# uc.net
KiCad netlist of a schematic drawn in Altium Designer
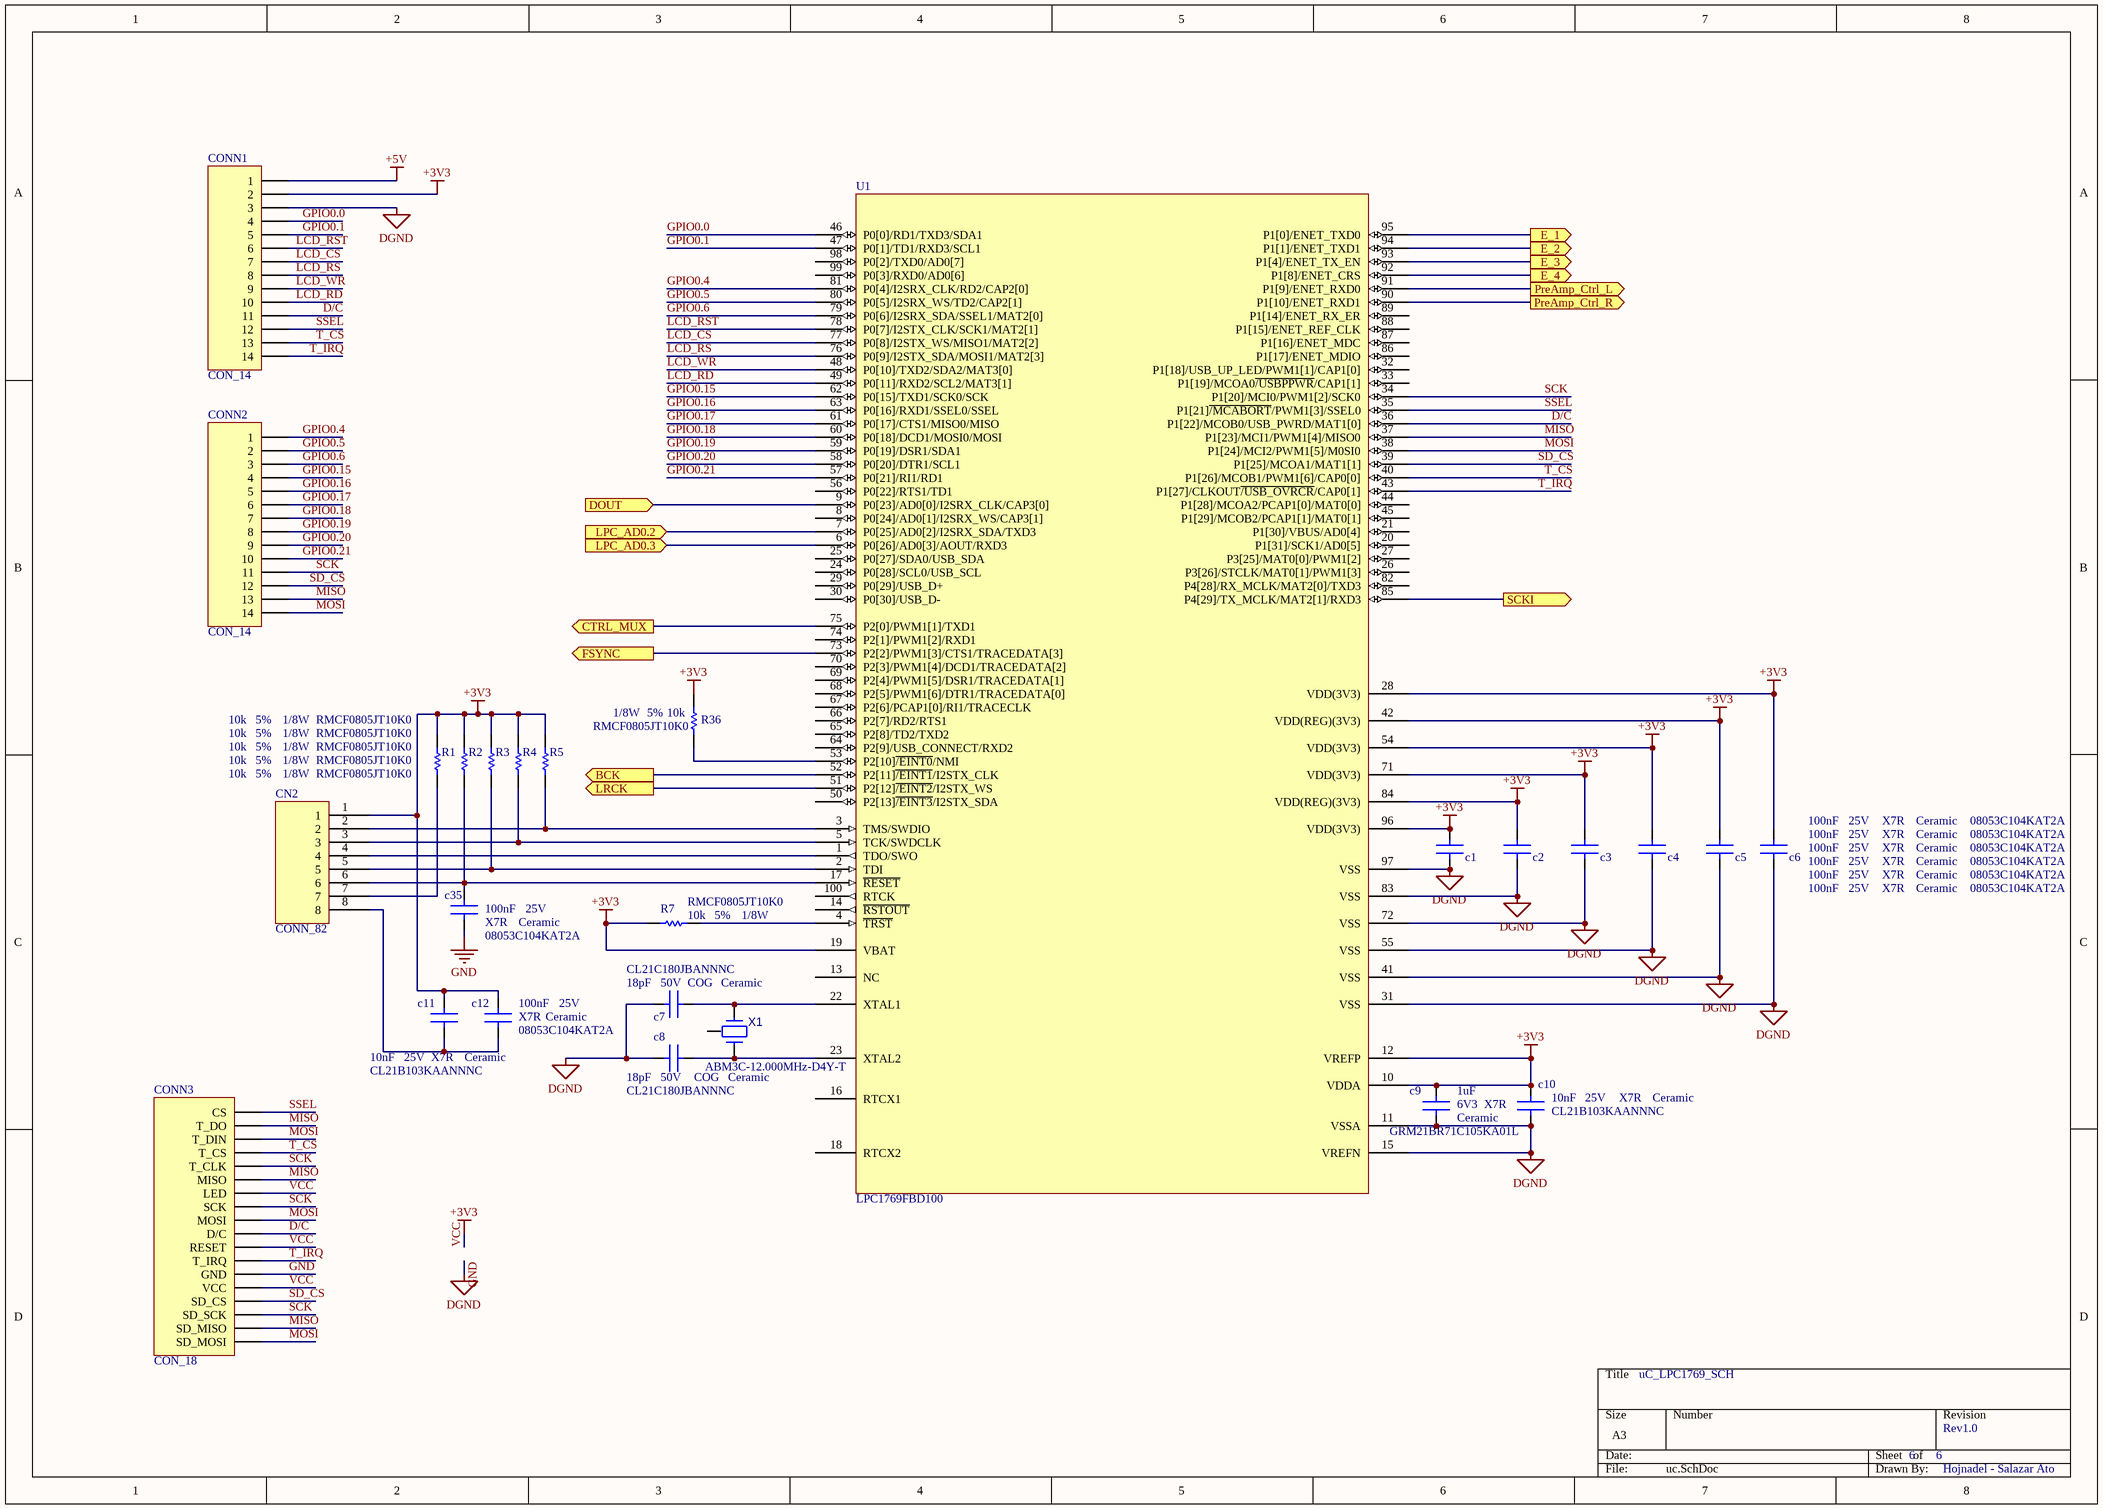
[diagram p0: uc.SchDoc]

(export (version "E")
  (design (tool "Eeschema 10.0.6"))
  (components
    (comp (ref "c1")
      (value "100nF 25V X7R Ceramic")
      (footprint "C_0805")
      (description "Capacitor")
      (fields
        (field (name "C") "100nF")
        (field (name "V") "25V")
        (field (name "PART NUMBER") "08053C104KAT2A")
        (field (name "TEMP COEF") "X7R")
        (field (name "MATERIAL") "Ceramic")
      )
      (libsource (lib "TDII_Lib_V2") (part "Cap1"))
    )
    (comp (ref "c2")
      (value "100nF 25V X7R Ceramic")
      (footprint "C_0805")
      (description "Capacitor")
      (fields
        (field (name "C") "100nF")
        (field (name "V") "25V")
        (field (name "PART NUMBER") "08053C104KAT2A")
        (field (name "TEMP COEF") "X7R")
        (field (name "MATERIAL") "Ceramic")
      )
      (libsource (lib "TDII_Lib_V2") (part "Cap1"))
    )
    (comp (ref "c3")
      (value "100nF 25V X7R Ceramic")
      (footprint "C_0805")
      (description "Capacitor")
      (fields
        (field (name "C") "100nF")
        (field (name "V") "25V")
        (field (name "PART NUMBER") "08053C104KAT2A")
        (field (name "TEMP COEF") "X7R")
        (field (name "MATERIAL") "Ceramic")
      )
      (libsource (lib "TDII_Lib_V2") (part "Cap1"))
    )
    (comp (ref "c4")
      (value "100nF 25V X7R Ceramic")
      (footprint "C_0805")
      (description "Capacitor")
      (fields
        (field (name "C") "100nF")
        (field (name "V") "25V")
        (field (name "PART NUMBER") "08053C104KAT2A")
        (field (name "TEMP COEF") "X7R")
        (field (name "MATERIAL") "Ceramic")
      )
      (libsource (lib "TDII_Lib_V2") (part "Cap1"))
    )
    (comp (ref "c5")
      (value "100nF 25V X7R Ceramic")
      (footprint "C_0805")
      (description "Capacitor")
      (fields
        (field (name "C") "100nF")
        (field (name "V") "25V")
        (field (name "PART NUMBER") "08053C104KAT2A")
        (field (name "TEMP COEF") "X7R")
        (field (name "MATERIAL") "Ceramic")
      )
      (libsource (lib "TDII_Lib_V2") (part "Cap1"))
    )
    (comp (ref "c6")
      (value "100nF 25V X7R Ceramic")
      (footprint "C_0805")
      (description "Capacitor")
      (fields
        (field (name "C") "100nF")
        (field (name "V") "25V")
        (field (name "PART NUMBER") "08053C104KAT2A")
        (field (name "TEMP COEF") "X7R")
        (field (name "MATERIAL") "Ceramic")
      )
      (libsource (lib "TDII_Lib_V2") (part "Cap1"))
    )
    (comp (ref "c7")
      (value "18pF 50V COG Ceramic")
      (footprint "C_0805")
      (description "Capacitor")
      (fields
        (field (name "C") "18pF")
        (field (name "V") "50V")
        (field (name "PART NUMBER") "CL21C180JBANNNC")
        (field (name "TEMP COEF") "COG")
        (field (name "MATERIAL") "Ceramic")
      )
      (libsource (lib "TDII_Lib_V2") (part "Cap1"))
    )
    (comp (ref "c8")
      (value "18pF 50V COG Ceramic")
      (footprint "C_0805")
      (description "Capacitor")
      (fields
        (field (name "C") "18pF")
        (field (name "V") "50V")
        (field (name "PART NUMBER") "CL21C180JBANNNC")
        (field (name "TEMP COEF") "COG")
        (field (name "MATERIAL") "Ceramic")
      )
      (libsource (lib "TDII_Lib_V2") (part "Cap1"))
    )
    (comp (ref "c9")
      (value "1uF 6V3 X7R Ceramic")
      (footprint "C_0805")
      (description "Capacitor")
      (fields
        (field (name "C") "1uF")
        (field (name "V") "6V3")
        (field (name "PART NUMBER") "GRM21BR71C105KA01L")
        (field (name "TEMP COEF") "X7R")
        (field (name "MATERIAL") "Ceramic")
      )
      (libsource (lib "TDII_Lib_V2") (part "Cap1"))
    )
    (comp (ref "c10")
      (value "10nF 25V X7R Ceramic")
      (footprint "C_0805")
      (description "Capacitor")
      (fields
        (field (name "C") "10nF")
        (field (name "V") "25V")
        (field (name "PART NUMBER") "CL21B103KAANNNC")
        (field (name "TEMP COEF") "X7R")
        (field (name "MATERIAL") "Ceramic")
      )
      (libsource (lib "TDII_Lib_V2") (part "Cap1"))
    )
    (comp (ref "c11")
      (value "10nF 25V X7R Ceramic")
      (footprint "C_0805")
      (description "Capacitor")
      (fields
        (field (name "C") "10nF")
        (field (name "V") "25V")
        (field (name "PART NUMBER") "CL21B103KAANNNC")
        (field (name "TEMP COEF") "X7R")
        (field (name "MATERIAL") "Ceramic")
      )
      (libsource (lib "TDII_Lib_V2") (part "Cap1"))
    )
    (comp (ref "c12")
      (value "100nF 25V X7R Ceramic")
      (footprint "C_0805")
      (description "Capacitor")
      (fields
        (field (name "C") "100nF")
        (field (name "V") "25V")
        (field (name "PART NUMBER") "08053C104KAT2A")
        (field (name "TEMP COEF") "X7R")
        (field (name "MATERIAL") "Ceramic")
      )
      (libsource (lib "TDII_Lib_V2") (part "C?"))
    )
    (comp (ref "c35")
      (value "100nF 25V X7R Ceramic")
      (footprint "C_0805")
      (description "Capacitor")
      (fields
        (field (name "C") "100nF")
        (field (name "V") "25V")
        (field (name "TEMP COEF") "X7R")
        (field (name "PART NUMBER") "08053C104KAT2A")
        (field (name "MATERIAL") "Ceramic")
      )
      (libsource (lib "TDII_Lib_V2") (part "C?"))
    )
    (comp (ref "CN2")
      (value "CONN_82")
      (footprint "HDR_M_08P_0.1")
      (libsource (lib "TDII_Lib") (part "CONN_82"))
    )
    (comp (ref "CONN1")
      (value "CON_14")
      (footprint "1x14x2.54 Pin Header TH V")
      (description "CONN TFT 3.5")
      (libsource (lib "TDII_Lib_V2") (part "CON_14"))
    )
    (comp (ref "CONN2")
      (value "CON_14")
      (footprint "1x14x2.54 Pin Header TH V")
      (description "CONN TFT 3.5")
      (libsource (lib "TDII_Lib_V2") (part "CON_14"))
    )
    (comp (ref "CONN3")
      (value "CON_18")
      (footprint "2x9x2.54 Pin Header TH V")
      (description "CON_TFT_2.8")
      (libsource (lib "TDII_Lib_V2") (part "CON_18"))
    )
    (comp (ref "R1")
      (value "10k")
      (footprint "R_0805")
      (description "Resistor")
      (fields
        (field (name "POWER") "1/8W")
        (field (name "PART NUMBER") "RMCF0805JT10K0")
        (field (name "TOLERANCE") "5%")
        (field (name "Comment") "10k 5% 1/8W")
      )
      (libsource (lib "TDII_Lib") (part "Res1"))
    )
    (comp (ref "R2")
      (value "10k")
      (footprint "R_0805")
      (description "Resistor")
      (fields
        (field (name "PART NUMBER") "RMCF0805JT10K0")
        (field (name "TOLERANCE") "5%")
        (field (name "POWER") "1/8W")
        (field (name "Comment") "10k 5% 1/8W")
      )
      (libsource (lib "TDII_Lib") (part "Res1"))
    )
    (comp (ref "R3")
      (value "10k")
      (footprint "R_0805")
      (description "Resistor")
      (fields
        (field (name "POWER") "1/8W")
        (field (name "PART NUMBER") "RMCF0805JT10K0")
        (field (name "TOLERANCE") "5%")
        (field (name "Comment") "10k 5% 1/8W")
      )
      (libsource (lib "TDII_Lib") (part "Res1"))
    )
    (comp (ref "R4")
      (value "10k")
      (footprint "R_0805")
      (description "Resistor")
      (fields
        (field (name "POWER") "1/8W")
        (field (name "PART NUMBER") "RMCF0805JT10K0")
        (field (name "TOLERANCE") "5%")
        (field (name "Comment") "10k 5% 1/8W")
      )
      (libsource (lib "TDII_Lib") (part "Res1"))
    )
    (comp (ref "R5")
      (value "10k")
      (footprint "R_0805")
      (description "Resistor")
      (fields
        (field (name "POWER") "1/8W")
        (field (name "PART NUMBER") "RMCF0805JT10K0")
        (field (name "TOLERANCE") "5%")
        (field (name "Comment") "10k 5% 1/8W")
      )
      (libsource (lib "TDII_Lib") (part "Res1"))
    )
    (comp (ref "R7")
      (value "10k")
      (footprint "R_0805")
      (description "Resistor")
      (fields
        (field (name "POWER") "1/8W")
        (field (name "PART NUMBER") "RMCF0805JT10K0")
        (field (name "TOLERANCE") "5%")
        (field (name "Comment") "10k 5% 1/8W")
      )
      (libsource (lib "TDII_Lib") (part "Res1"))
    )
    (comp (ref "R36")
      (value "10k")
      (footprint "R_0805")
      (description "Resistor")
      (fields
        (field (name "POWER") "1/8W")
        (field (name "PART NUMBER") "RMCF0805JT10K0")
        (field (name "TOLERANCE") "5%")
        (field (name "Comment") "10k 5% 1/8W")
      )
      (libsource (lib "TDII_Lib_V2") (part "Res1"))
    )
    (comp (ref "U1")
      (value "LPC1769FBD100")
      (footprint "LQFP100")
      (description "CPU Cortex M3")
      (libsource (lib "TDII_Lib_V2") (part "LPC1768FBD100"))
    )
    (comp (ref "X1")
      (value "XTAL_HF")
      (footprint "ABMC_XTAL")
      (description "Crystal")
      (fields (field (name "PART NUMBER") "ABM3C-12.000MHz-D4Y-T"))
      (libsource (lib "TDII_Lib_V2") (part "XTAL_HF"))
    )
  )
  (nets
    (net (code "1") (name "+3V3") (class "Default")
      (node (ref "CN2") (pin "1") (pinfunction "1_1") (pintype "passive"))
      (node (ref "CONN1") (pin "2") (pinfunction "2_2") (pintype "passive"))
      (node (ref "CONN3") (pin "11") (pinfunction "RESET_11") (pintype "passive"))
      (node (ref "CONN3") (pin "14") (pinfunction "VCC_14") (pintype "passive"))
      (node (ref "CONN3") (pin "7") (pinfunction "LED_7") (pintype "passive"))
      (node (ref "R1") (pin "2") (pinfunction "2_2") (pintype "passive"))
      (node (ref "R2") (pin "2") (pinfunction "2_2") (pintype "passive"))
      (node (ref "R3") (pin "2") (pinfunction "2_2") (pintype "passive"))
      (node (ref "R36") (pin "2") (pinfunction "2_2") (pintype "passive"))
      (node (ref "R4") (pin "2") (pinfunction "2_2") (pintype "passive"))
      (node (ref "R5") (pin "2") (pinfunction "2_2") (pintype "passive"))
      (node (ref "R7") (pin "2") (pinfunction "2_2") (pintype "passive"))
      (node (ref "U1") (pin "10") (pinfunction "VDDA_10") (pintype "power_in"))
      (node (ref "U1") (pin "12") (pinfunction "VREFP_12") (pintype "power_in"))
      (node (ref "U1") (pin "19") (pinfunction "VBAT_19") (pintype "power_in"))
      (node (ref "U1") (pin "28") (pinfunction "VDD(3V3)_28") (pintype "power_in"))
      (node (ref "U1") (pin "42") (pinfunction "VDD(REG)(3V3)_42") (pintype "power_in"))
      (node (ref "U1") (pin "54") (pinfunction "VDD(3V3)_54") (pintype "power_in"))
      (node (ref "U1") (pin "71") (pinfunction "VDD(3V3)_71") (pintype "power_in"))
      (node (ref "U1") (pin "84") (pinfunction "VDD(REG)(3V3)_84") (pintype "power_in"))
      (node (ref "U1") (pin "96") (pinfunction "VDD(3V3)_96") (pintype "power_in"))
      (node (ref "c1") (pin "1") (pinfunction "1_1") (pintype "passive"))
      (node (ref "c10") (pin "1") (pinfunction "1_1") (pintype "passive"))
      (node (ref "c11") (pin "1") (pinfunction "1_1") (pintype "passive"))
      (node (ref "c12") (pin "1") (pinfunction "1_1") (pintype "passive"))
      (node (ref "c2") (pin "1") (pinfunction "1_1") (pintype "passive"))
      (node (ref "c3") (pin "1") (pinfunction "1_1") (pintype "passive"))
      (node (ref "c4") (pin "1") (pinfunction "1_1") (pintype "passive"))
      (node (ref "c5") (pin "1") (pinfunction "1_1") (pintype "passive"))
      (node (ref "c6") (pin "1") (pinfunction "1_1") (pintype "passive"))
      (node (ref "c9") (pin "1") (pinfunction "1_1") (pintype "passive"))
    )
    (net (code "2") (name "+5V") (class "Default")
      (node (ref "CONN1") (pin "1") (pinfunction "1_1") (pintype "passive"))
    )
    (net (code "3") (name "/BCK") (class "Default")
      (node (ref "U1") (pin "52") (pinfunction "P2[11]~{/EINT1}/I2STX_CLK_52") (pintype "bidirectional"))
    )
    (net (code "4") (name "/CTRL_MUX") (class "Default")
      (node (ref "U1") (pin "75") (pinfunction "P2[0]/PWM1[1]/TXD1_75") (pintype "bidirectional"))
    )
    (net (code "5") (name "/DOUT") (class "Default")
      (node (ref "U1") (pin "9") (pinfunction "P0[23]/AD0[0]/I2SRX_CLK/CAP3[0]_9") (pintype "bidirectional"))
    )
    (net (code "6") (name "/D{slash}C") (class "Default")
      (node (ref "CONN1") (pin "11") (pinfunction "11_11") (pintype "passive"))
      (node (ref "CONN3") (pin "10") (pinfunction "D/C_10") (pintype "passive"))
      (node (ref "U1") (pin "36") (pinfunction "P1[22]/MCOB0/USB_PWRD/MAT1[0]_36") (pintype "bidirectional"))
    )
    (net (code "7") (name "/E_1") (class "Default")
      (node (ref "U1") (pin "95") (pinfunction "P1[0]/ENET_TXD0_95") (pintype "bidirectional"))
    )
    (net (code "8") (name "/E_2") (class "Default")
      (node (ref "U1") (pin "94") (pinfunction "P1[1]/ENET_TXD1_94") (pintype "bidirectional"))
    )
    (net (code "9") (name "/E_3") (class "Default")
      (node (ref "U1") (pin "93") (pinfunction "P1[4]/ENET_TX_EN_93") (pintype "bidirectional"))
    )
    (net (code "10") (name "/E_4") (class "Default")
      (node (ref "U1") (pin "92") (pinfunction "P1[8]/ENET_CRS_92") (pintype "bidirectional"))
    )
    (net (code "11") (name "/FSYNC") (class "Default")
      (node (ref "U1") (pin "73") (pinfunction "P2[2]/PWM1[3]/CTS1/TRACEDATA[3]_73") (pintype "bidirectional"))
    )
    (net (code "12") (name "/GPIO0.0") (class "Default")
      (node (ref "CONN1") (pin "4") (pinfunction "4_4") (pintype "passive"))
      (node (ref "U1") (pin "46") (pinfunction "P0[0]/RD1/TXD3/SDA1_46") (pintype "bidirectional"))
    )
    (net (code "13") (name "/GPIO0.1") (class "Default")
      (node (ref "CONN1") (pin "5") (pinfunction "5_5") (pintype "passive"))
      (node (ref "U1") (pin "47") (pinfunction "P0[1]/TD1/RXD3/SCL1_47") (pintype "bidirectional"))
    )
    (net (code "14") (name "/GPIO0.4") (class "Default")
      (node (ref "CONN2") (pin "1") (pinfunction "1_1") (pintype "passive"))
      (node (ref "U1") (pin "81") (pinfunction "P0[4]/I2SRX_CLK/RD2/CAP2[0]_81") (pintype "bidirectional"))
    )
    (net (code "15") (name "/GPIO0.5") (class "Default")
      (node (ref "CONN2") (pin "2") (pinfunction "2_2") (pintype "passive"))
      (node (ref "U1") (pin "80") (pinfunction "P0[5]/I2SRX_WS/TD2/CAP2[1]_80") (pintype "bidirectional"))
    )
    (net (code "16") (name "/GPIO0.6") (class "Default")
      (node (ref "CONN2") (pin "3") (pinfunction "3_3") (pintype "passive"))
      (node (ref "U1") (pin "79") (pinfunction "P0[6]/I2SRX_SDA/SSEL1/MAT2[0]_79") (pintype "bidirectional"))
    )
    (net (code "17") (name "/GPIO0.15") (class "Default")
      (node (ref "CONN2") (pin "4") (pinfunction "4_4") (pintype "passive"))
      (node (ref "U1") (pin "62") (pinfunction "P0[15]/TXD1/SCK0/SCK_62") (pintype "bidirectional"))
    )
    (net (code "18") (name "/GPIO0.16") (class "Default")
      (node (ref "CONN2") (pin "5") (pinfunction "5_5") (pintype "passive"))
      (node (ref "U1") (pin "63") (pinfunction "P0[16]/RXD1/SSEL0/SSEL_63") (pintype "bidirectional"))
    )
    (net (code "19") (name "/GPIO0.17") (class "Default")
      (node (ref "CONN2") (pin "6") (pinfunction "6_6") (pintype "passive"))
      (node (ref "U1") (pin "61") (pinfunction "P0[17]/CTS1/MISO0/MISO_61") (pintype "bidirectional"))
    )
    (net (code "20") (name "/GPIO0.18") (class "Default")
      (node (ref "CONN2") (pin "7") (pinfunction "7_7") (pintype "passive"))
      (node (ref "U1") (pin "60") (pinfunction "P0[18]/DCD1/MOSI0/MOSI_60") (pintype "bidirectional"))
    )
    (net (code "21") (name "/GPIO0.19") (class "Default")
      (node (ref "CONN2") (pin "8") (pinfunction "8_8") (pintype "passive"))
      (node (ref "U1") (pin "59") (pinfunction "P0[19]/DSR1/SDA1_59") (pintype "bidirectional"))
    )
    (net (code "22") (name "/GPIO0.20") (class "Default")
      (node (ref "CONN2") (pin "9") (pinfunction "9_9") (pintype "passive"))
      (node (ref "U1") (pin "58") (pinfunction "P0[20]/DTR1/SCL1_58") (pintype "bidirectional"))
    )
    (net (code "23") (name "/GPIO0.21") (class "Default")
      (node (ref "CONN2") (pin "10") (pinfunction "10_10") (pintype "passive"))
      (node (ref "U1") (pin "57") (pinfunction "P0[21]/RI1/RD1_57") (pintype "bidirectional"))
    )
    (net (code "24") (name "/LCD_CS") (class "Default")
      (node (ref "CONN1") (pin "7") (pinfunction "7_7") (pintype "passive"))
      (node (ref "U1") (pin "77") (pinfunction "P0[8]/I2STX_WS/MISO1/MAT2[2]_77") (pintype "bidirectional"))
    )
    (net (code "25") (name "/LCD_RD") (class "Default")
      (node (ref "CONN1") (pin "10") (pinfunction "10_10") (pintype "passive"))
      (node (ref "U1") (pin "49") (pinfunction "P0[11]/RXD2/SCL2/MAT3[1]_49") (pintype "bidirectional"))
    )
    (net (code "26") (name "/LCD_RS") (class "Default")
      (node (ref "CONN1") (pin "8") (pinfunction "8_8") (pintype "passive"))
      (node (ref "U1") (pin "76") (pinfunction "P0[9]/I2STX_SDA/MOSI1/MAT2[3]_76") (pintype "bidirectional"))
    )
    (net (code "27") (name "/LCD_RST") (class "Default")
      (node (ref "CONN1") (pin "6") (pinfunction "6_6") (pintype "passive"))
      (node (ref "U1") (pin "78") (pinfunction "P0[7]/I2STX_CLK/SCK1/MAT2[1]_78") (pintype "bidirectional"))
    )
    (net (code "28") (name "/LCD_WR") (class "Default")
      (node (ref "CONN1") (pin "9") (pinfunction "9_9") (pintype "passive"))
      (node (ref "U1") (pin "48") (pinfunction "P0[10]/TXD2/SDA2/MAT3[0]_48") (pintype "bidirectional"))
    )
    (net (code "29") (name "/LPC_AD0.2") (class "Default")
      (node (ref "U1") (pin "7") (pinfunction "P0[25]/AD0[2]/I2SRX_SDA/TXD3_7") (pintype "bidirectional"))
    )
    (net (code "30") (name "/LPC_AD0.3") (class "Default")
      (node (ref "U1") (pin "6") (pinfunction "P0[26]/AD0[3]/AOUT/RXD3_6") (pintype "bidirectional"))
    )
    (net (code "31") (name "/LRCK") (class "Default")
      (node (ref "U1") (pin "51") (pinfunction "P2[12]~{/EINT2}/I2STX_WS_51") (pintype "bidirectional"))
    )
    (net (code "32") (name "/MISO") (class "Default")
      (node (ref "CONN2") (pin "13") (pinfunction "13_13") (pintype "passive"))
      (node (ref "CONN3") (pin "17") (pinfunction "SD_MISO_17") (pintype "passive"))
      (node (ref "CONN3") (pin "2") (pinfunction "T_DO_2") (pintype "passive"))
      (node (ref "CONN3") (pin "6") (pinfunction "MISO_6") (pintype "passive"))
      (node (ref "U1") (pin "37") (pinfunction "P1[23]/MCI1/PWM1[4]/MISO0_37") (pintype "bidirectional"))
    )
    (net (code "33") (name "/MOSI") (class "Default")
      (node (ref "CONN2") (pin "14") (pinfunction "14_14") (pintype "passive"))
      (node (ref "CONN3") (pin "18") (pinfunction "SD_MOSI_18") (pintype "passive"))
      (node (ref "CONN3") (pin "3") (pinfunction "T_DIN_3") (pintype "passive"))
      (node (ref "CONN3") (pin "9") (pinfunction "MOSI_9") (pintype "passive"))
      (node (ref "U1") (pin "38") (pinfunction "P1[24]/MCI2/PWM1[5]/M0SI0_38") (pintype "bidirectional"))
    )
    (net (code "34") (name "/PreAmp_Ctrl_L") (class "Default")
      (node (ref "U1") (pin "91") (pinfunction "P1[9]/ENET_RXD0_91") (pintype "bidirectional"))
    )
    (net (code "35") (name "/PreAmp_Ctrl_R") (class "Default")
      (node (ref "U1") (pin "90") (pinfunction "P1[10]/ENET_RXD1_90") (pintype "bidirectional"))
    )
    (net (code "36") (name "/SCK") (class "Default")
      (node (ref "CONN2") (pin "11") (pinfunction "11_11") (pintype "passive"))
      (node (ref "CONN3") (pin "16") (pinfunction "SD_SCK_16") (pintype "passive"))
      (node (ref "CONN3") (pin "5") (pinfunction "T_CLK_5") (pintype "passive"))
      (node (ref "CONN3") (pin "8") (pinfunction "SCK_8") (pintype "passive"))
      (node (ref "U1") (pin "34") (pinfunction "P1[20]/MCI0/PWM1[2]/SCK0_34") (pintype "bidirectional"))
    )
    (net (code "37") (name "/SCKI") (class "Default")
      (node (ref "U1") (pin "85") (pinfunction "P4[29]/TX_MCLK/MAT2[1]/RXD3_85") (pintype "bidirectional"))
    )
    (net (code "38") (name "/SD_CS") (class "Default")
      (node (ref "CONN2") (pin "12") (pinfunction "12_12") (pintype "passive"))
      (node (ref "CONN3") (pin "15") (pinfunction "SD_CS_15") (pintype "passive"))
      (node (ref "U1") (pin "39") (pinfunction "P1[25]/MCOA1/MAT1[1]_39") (pintype "bidirectional"))
    )
    (net (code "39") (name "/SSEL") (class "Default")
      (node (ref "CONN1") (pin "12") (pinfunction "12_12") (pintype "passive"))
      (node (ref "CONN3") (pin "1") (pinfunction "CS_1") (pintype "passive"))
      (node (ref "U1") (pin "35") (pinfunction "P1[21]~{/MCABORT}/PWM1[3]/SSEL0_35") (pintype "bidirectional"))
    )
    (net (code "40") (name "/T_CS") (class "Default")
      (node (ref "CONN1") (pin "13") (pinfunction "13_13") (pintype "passive"))
      (node (ref "CONN3") (pin "4") (pinfunction "T_CS_4") (pintype "passive"))
      (node (ref "U1") (pin "40") (pinfunction "P1[26]/MCOB1/PWM1[6]/CAP0[0]_40") (pintype "bidirectional"))
    )
    (net (code "41") (name "/T_IRQ") (class "Default")
      (node (ref "CONN1") (pin "14") (pinfunction "14_14") (pintype "passive"))
      (node (ref "CONN3") (pin "12") (pinfunction "T_IRQ_12") (pintype "passive"))
      (node (ref "U1") (pin "43") (pinfunction "P1[27]/CLKOUT~{/USB_OVRCR}/CAP0[1]_43") (pintype "bidirectional"))
    )
    (net (code "42") (name "DGND") (class "Default")
      (node (ref "CONN1") (pin "3") (pinfunction "3_3") (pintype "passive"))
      (node (ref "CONN3") (pin "13") (pinfunction "GND_13") (pintype "passive"))
      (node (ref "U1") (pin "11") (pinfunction "VSSA_11") (pintype "power_in"))
      (node (ref "U1") (pin "15") (pinfunction "VREFN_15") (pintype "power_in"))
      (node (ref "U1") (pin "31") (pinfunction "VSS_31") (pintype "power_in"))
      (node (ref "U1") (pin "41") (pinfunction "VSS_41") (pintype "power_in"))
      (node (ref "U1") (pin "55") (pinfunction "VSS_55") (pintype "power_in"))
      (node (ref "U1") (pin "72") (pinfunction "VSS_72") (pintype "power_in"))
      (node (ref "U1") (pin "83") (pinfunction "VSS_83") (pintype "power_in"))
      (node (ref "U1") (pin "97") (pinfunction "VSS_97") (pintype "power_in"))
      (node (ref "c1") (pin "2") (pinfunction "2_2") (pintype "passive"))
      (node (ref "c10") (pin "2") (pinfunction "2_2") (pintype "passive"))
      (node (ref "c2") (pin "2") (pinfunction "2_2") (pintype "passive"))
      (node (ref "c3") (pin "2") (pinfunction "2_2") (pintype "passive"))
      (node (ref "c35") (pin "2") (pinfunction "2_2") (pintype "passive"))
      (node (ref "c4") (pin "2") (pinfunction "2_2") (pintype "passive"))
      (node (ref "c5") (pin "2") (pinfunction "2_2") (pintype "passive"))
      (node (ref "c6") (pin "2") (pinfunction "2_2") (pintype "passive"))
      (node (ref "c7") (pin "1") (pinfunction "1_1") (pintype "passive"))
      (node (ref "c8") (pin "1") (pinfunction "1_1") (pintype "passive"))
      (node (ref "c9") (pin "2") (pinfunction "2_2") (pintype "passive"))
    )
    (net (code "43") (name "Net-(CN2-Pad7)") (class "Default")
      (node (ref "CN2") (pin "7") (pinfunction "7_7") (pintype "passive"))
      (node (ref "R1") (pin "1") (pinfunction "1_1") (pintype "passive"))
    )
    (net (code "44") (name "Net-(CN2-Pad8)") (class "Default")
      (node (ref "CN2") (pin "8") (pinfunction "8_8") (pintype "passive"))
      (node (ref "c11") (pin "2") (pinfunction "2_2") (pintype "passive"))
      (node (ref "c12") (pin "2") (pinfunction "2_2") (pintype "passive"))
    )
    (net (code "45") (name "Net-(U1-P2[10]~{{slash}EINT0}{slash}NMI)") (class "Default")
      (node (ref "R36") (pin "1") (pinfunction "1_1") (pintype "passive"))
      (node (ref "U1") (pin "53") (pinfunction "P2[10]~{/EINT0}/NMI_53") (pintype "bidirectional"))
    )
    (net (code "46") (name "Net-(U1-TCK{slash}SWDCLK)") (class "Default")
      (node (ref "CN2") (pin "3") (pinfunction "3_3") (pintype "passive"))
      (node (ref "R4") (pin "1") (pinfunction "1_1") (pintype "passive"))
      (node (ref "U1") (pin "5") (pinfunction "TCK/SWDCLK_5") (pintype "input"))
    )
    (net (code "47") (name "Net-(U1-TDI)") (class "Default")
      (node (ref "CN2") (pin "5") (pinfunction "5_5") (pintype "passive"))
      (node (ref "R3") (pin "1") (pinfunction "1_1") (pintype "passive"))
      (node (ref "U1") (pin "2") (pinfunction "TDI_2") (pintype "input"))
    )
    (net (code "48") (name "Net-(U1-TDO{slash}SWO)") (class "Default")
      (node (ref "CN2") (pin "4") (pinfunction "4_4") (pintype "passive"))
      (node (ref "U1") (pin "1") (pinfunction "TDO/SWO_1") (pintype "output"))
    )
    (net (code "49") (name "Net-(U1-TMS{slash}SWDIO)") (class "Default")
      (node (ref "CN2") (pin "2") (pinfunction "2_2") (pintype "passive"))
      (node (ref "R5") (pin "1") (pinfunction "1_1") (pintype "passive"))
      (node (ref "U1") (pin "3") (pinfunction "TMS/SWDIO_3") (pintype "input"))
    )
    (net (code "50") (name "Net-(U1-XTAL1)") (class "Default")
      (node (ref "U1") (pin "22") (pinfunction "XTAL1_22") (pintype "passive"))
      (node (ref "X1") (pin "1") (pinfunction "1_1") (pintype "passive"))
      (node (ref "c7") (pin "2") (pinfunction "2_2") (pintype "passive"))
    )
    (net (code "51") (name "Net-(U1-XTAL2)") (class "Default")
      (node (ref "U1") (pin "23") (pinfunction "XTAL2_23") (pintype "passive"))
      (node (ref "X1") (pin "3") (pinfunction "3_3") (pintype "passive"))
      (node (ref "c8") (pin "2") (pinfunction "2_2") (pintype "passive"))
    )
    (net (code "52") (name "Net-(U1-~{RESET})") (class "Default")
      (node (ref "CN2") (pin "6") (pinfunction "6_6") (pintype "passive"))
      (node (ref "R2") (pin "1") (pinfunction "1_1") (pintype "passive"))
      (node (ref "U1") (pin "17") (pinfunction "~{RESET}_17") (pintype "input"))
      (node (ref "c35") (pin "1") (pinfunction "1_1") (pintype "passive"))
    )
    (net (code "53") (name "Net-(U1-~{TRST})") (class "Default")
      (node (ref "R7") (pin "1") (pinfunction "1_1") (pintype "passive"))
      (node (ref "U1") (pin "4") (pinfunction "~{TRST}_4") (pintype "input"))
    )
    (net (code "54") (name "Net-(X1-GND)") (class "Default")
      (node (ref "X1") (pin "2") (pinfunction "GND_2") (pintype "passive"))
      (node (ref "X1") (pin "4") (pinfunction "4_4") (pintype "passive"))
    )
    (net (code "55") (name "unconnected-(U1-NC-Pad13)") (class "Default")
      (node (ref "U1") (pin "13") (pinfunction "NC_13") (pintype "passive"))
    )
    (net (code "56") (name "unconnected-(U1-P0[2]{slash}TXD0{slash}AD0[7]-Pad98)") (class "Default")
      (node (ref "U1") (pin "98") (pinfunction "P0[2]/TXD0/AD0[7]_98") (pintype "bidirectional"))
    )
    (net (code "57") (name "unconnected-(U1-P0[3]{slash}RXD0{slash}AD0[6]-Pad99)") (class "Default")
      (node (ref "U1") (pin "99") (pinfunction "P0[3]/RXD0/AD0[6]_99") (pintype "bidirectional"))
    )
    (net (code "58") (name "unconnected-(U1-P0[22]{slash}RTS1{slash}TD1-Pad56)") (class "Default")
      (node (ref "U1") (pin "56") (pinfunction "P0[22]/RTS1/TD1_56") (pintype "bidirectional"))
    )
    (net (code "59") (name "unconnected-(U1-P0[24]{slash}AD0[1]{slash}I2SRX_WS{slash}CAP3[1]-Pad8)") (class "Default")
      (node (ref "U1") (pin "8") (pinfunction "P0[24]/AD0[1]/I2SRX_WS/CAP3[1]_8") (pintype "bidirectional"))
    )
    (net (code "60") (name "unconnected-(U1-P0[27]{slash}SDA0{slash}USB_SDA-Pad25)") (class "Default")
      (node (ref "U1") (pin "25") (pinfunction "P0[27]/SDA0/USB_SDA_25") (pintype "bidirectional"))
    )
    (net (code "61") (name "unconnected-(U1-P0[28]{slash}SCL0{slash}USB_SCL-Pad24)") (class "Default")
      (node (ref "U1") (pin "24") (pinfunction "P0[28]/SCL0/USB_SCL_24") (pintype "bidirectional"))
    )
    (net (code "62") (name "unconnected-(U1-P0[29]{slash}USB_D+-Pad29)") (class "Default")
      (node (ref "U1") (pin "29") (pinfunction "P0[29]/USB_D+_29") (pintype "bidirectional"))
    )
    (net (code "63") (name "unconnected-(U1-P0[30]{slash}USB_D--Pad30)") (class "Default")
      (node (ref "U1") (pin "30") (pinfunction "P0[30]/USB_D-_30") (pintype "bidirectional"))
    )
    (net (code "64") (name "unconnected-(U1-P1[14]{slash}ENET_RX_ER-Pad89)") (class "Default")
      (node (ref "U1") (pin "89") (pinfunction "P1[14]/ENET_RX_ER_89") (pintype "bidirectional"))
    )
    (net (code "65") (name "unconnected-(U1-P1[15]{slash}ENET_REF_CLK-Pad88)") (class "Default")
      (node (ref "U1") (pin "88") (pinfunction "P1[15]/ENET_REF_CLK_88") (pintype "bidirectional"))
    )
    (net (code "66") (name "unconnected-(U1-P1[16]{slash}ENET_MDC-Pad87)") (class "Default")
      (node (ref "U1") (pin "87") (pinfunction "P1[16]/ENET_MDC_87") (pintype "bidirectional"))
    )
    (net (code "67") (name "unconnected-(U1-P1[17]{slash}ENET_MDIO-Pad86)") (class "Default")
      (node (ref "U1") (pin "86") (pinfunction "P1[17]/ENET_MDIO_86") (pintype "bidirectional"))
    )
    (net (code "68") (name "unconnected-(U1-P1[18]{slash}USB_UP_LED{slash}PWM1[1]{slash}CAP1[0]-Pad32)") (class "Default")
      (node (ref "U1") (pin "32") (pinfunction "P1[18]/USB_UP_LED/PWM1[1]/CAP1[0]_32") (pintype "bidirectional"))
    )
    (net (code "69") (name "unconnected-(U1-P1[19]{slash}MCOA0~{{slash}USBPPWR}{slash}CAP1[1]-Pad33)") (class "Default")
      (node (ref "U1") (pin "33") (pinfunction "P1[19]/MCOA0~{/USBPPWR}/CAP1[1]_33") (pintype "bidirectional"))
    )
    (net (code "70") (name "unconnected-(U1-P1[28]{slash}MCOA2{slash}PCAP1[0]{slash}MAT0[0]-Pad44)") (class "Default")
      (node (ref "U1") (pin "44") (pinfunction "P1[28]/MCOA2/PCAP1[0]/MAT0[0]_44") (pintype "bidirectional"))
    )
    (net (code "71") (name "unconnected-(U1-P1[29]{slash}MCOB2{slash}PCAP1[1]{slash}MAT0[1]-Pad45)") (class "Default")
      (node (ref "U1") (pin "45") (pinfunction "P1[29]/MCOB2/PCAP1[1]/MAT0[1]_45") (pintype "bidirectional"))
    )
    (net (code "72") (name "unconnected-(U1-P1[30]{slash}VBUS{slash}AD0[4]-Pad21)") (class "Default")
      (node (ref "U1") (pin "21") (pinfunction "P1[30]/VBUS/AD0[4]_21") (pintype "bidirectional"))
    )
    (net (code "73") (name "unconnected-(U1-P1[31]{slash}SCK1{slash}AD0[5]-Pad20)") (class "Default")
      (node (ref "U1") (pin "20") (pinfunction "P1[31]/SCK1/AD0[5]_20") (pintype "bidirectional"))
    )
    (net (code "74") (name "unconnected-(U1-P2[1]{slash}PWM1[2]{slash}RXD1-Pad74)") (class "Default")
      (node (ref "U1") (pin "74") (pinfunction "P2[1]/PWM1[2]/RXD1_74") (pintype "bidirectional"))
    )
    (net (code "75") (name "unconnected-(U1-P2[3]{slash}PWM1[4]{slash}DCD1{slash}TRACEDATA[2]-Pad70)") (class "Default")
      (node (ref "U1") (pin "70") (pinfunction "P2[3]/PWM1[4]/DCD1/TRACEDATA[2]_70") (pintype "bidirectional"))
    )
    (net (code "76") (name "unconnected-(U1-P2[4]{slash}PWM1[5]{slash}DSR1{slash}TRACEDATA[1]-Pad69)") (class "Default")
      (node (ref "U1") (pin "69") (pinfunction "P2[4]/PWM1[5]/DSR1/TRACEDATA[1]_69") (pintype "bidirectional"))
    )
    (net (code "77") (name "unconnected-(U1-P2[5]{slash}PWM1[6]{slash}DTR1{slash}TRACEDATA[0]-Pad68)") (class "Default")
      (node (ref "U1") (pin "68") (pinfunction "P2[5]/PWM1[6]/DTR1/TRACEDATA[0]_68") (pintype "bidirectional"))
    )
    (net (code "78") (name "unconnected-(U1-P2[6]{slash}PCAP1[0]{slash}RI1{slash}TRACECLK-Pad67)") (class "Default")
      (node (ref "U1") (pin "67") (pinfunction "P2[6]/PCAP1[0]/RI1/TRACECLK_67") (pintype "bidirectional"))
    )
    (net (code "79") (name "unconnected-(U1-P2[7]{slash}RD2{slash}RTS1-Pad66)") (class "Default")
      (node (ref "U1") (pin "66") (pinfunction "P2[7]/RD2/RTS1_66") (pintype "bidirectional"))
    )
    (net (code "80") (name "unconnected-(U1-P2[8]{slash}TD2{slash}TXD2-Pad65)") (class "Default")
      (node (ref "U1") (pin "65") (pinfunction "P2[8]/TD2/TXD2_65") (pintype "bidirectional"))
    )
    (net (code "81") (name "unconnected-(U1-P2[9]{slash}USB_CONNECT{slash}RXD2-Pad64)") (class "Default")
      (node (ref "U1") (pin "64") (pinfunction "P2[9]/USB_CONNECT/RXD2_64") (pintype "bidirectional"))
    )
    (net (code "82") (name "unconnected-(U1-P2[13]~{{slash}EINT3}{slash}I2STX_SDA-Pad50)") (class "Default")
      (node (ref "U1") (pin "50") (pinfunction "P2[13]~{/EINT3}/I2STX_SDA_50") (pintype "bidirectional"))
    )
    (net (code "83") (name "unconnected-(U1-P3[25]{slash}MAT0[0]{slash}PWM1[2]-Pad27)") (class "Default")
      (node (ref "U1") (pin "27") (pinfunction "P3[25]/MAT0[0]/PWM1[2]_27") (pintype "bidirectional"))
    )
    (net (code "84") (name "unconnected-(U1-P3[26]{slash}STCLK{slash}MAT0[1]{slash}PWM1[3]-Pad26)") (class "Default")
      (node (ref "U1") (pin "26") (pinfunction "P3[26]/STCLK/MAT0[1]/PWM1[3]_26") (pintype "bidirectional"))
    )
    (net (code "85") (name "unconnected-(U1-P4[28]{slash}RX_MCLK{slash}MAT2[0]{slash}TXD3-Pad82)") (class "Default")
      (node (ref "U1") (pin "82") (pinfunction "P4[28]/RX_MCLK/MAT2[0]/TXD3_82") (pintype "bidirectional"))
    )
    (net (code "86") (name "unconnected-(U1-RTCK-Pad100)") (class "Default")
      (node (ref "U1") (pin "100") (pinfunction "RTCK_100") (pintype "output"))
    )
    (net (code "87") (name "unconnected-(U1-RTCX1-Pad16)") (class "Default")
      (node (ref "U1") (pin "16") (pinfunction "RTCX1_16") (pintype "passive"))
    )
    (net (code "88") (name "unconnected-(U1-RTCX2-Pad18)") (class "Default")
      (node (ref "U1") (pin "18") (pinfunction "RTCX2_18") (pintype "passive"))
    )
    (net (code "89") (name "unconnected-(U1-~{RSTOUT}-Pad14)") (class "Default")
      (node (ref "U1") (pin "14") (pinfunction "~{RSTOUT}_14") (pintype "output"))
    )
  )
)
